# usb.net
KiCad netlist of a schematic drawn in Altium Designer
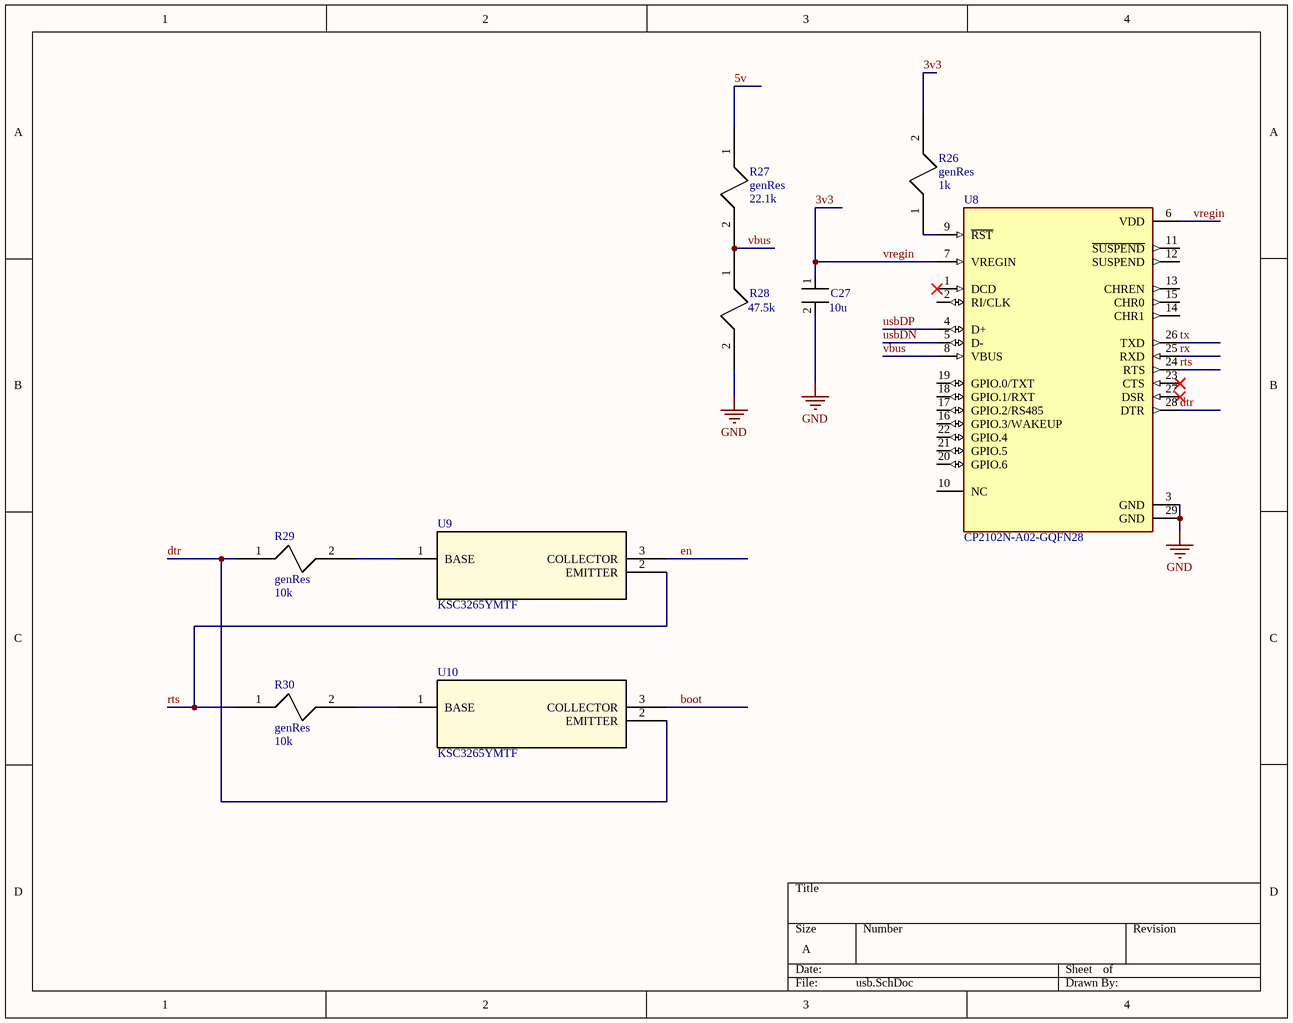
[diagram p0: usb.SchDoc]

(export (version "E")
  (design (tool "Eeschema 10.0.6"))
  (components
    (comp (ref "C27")
      (value "genCap")
      (footprint "GeneralCap")
      (description "C6119842")
      (fields (field (name "C") "10u"))
      (libsource (lib "seniorDesign") (part "genCap"))
    )
    (comp (ref "R26")
      (value "genRes")
      (footprint "GeneralCap")
      (description "C22548")
      (fields (field (name "R") "1k"))
      (libsource (lib "seniorDesign") (part "genRes"))
    )
    (comp (ref "R27")
      (value "genRes")
      (footprint "GeneralCap")
      (description "C137768")
      (fields (field (name "R") "22.1k"))
      (libsource (lib "seniorDesign") (part "genRes"))
    )
    (comp (ref "R28")
      (value "genRes")
      (footprint "GeneralCap")
      (description "C705990")
      (fields (field (name "R") "47.5k"))
      (libsource (lib "seniorDesign") (part "genRes"))
    )
    (comp (ref "R29")
      (value "genRes")
      (footprint "GeneralCap")
      (description "C98220")
      (fields (field (name "R") "10k"))
      (libsource (lib "seniorDesign") (part "genRes"))
    )
    (comp (ref "R30")
      (value "genRes")
      (footprint "GeneralCap")
      (description "C98220")
      (fields (field (name "R") "10k"))
      (libsource (lib "seniorDesign") (part "genRes"))
    )
    (comp (ref "U8")
      (value "CP2102N-A02-GQFN28")
      (footprint "QFN50P500X500X80-29N")
      (description "C1550553")
      (fields (field (name "MF") "Silicon Labs"))
      (libsource (lib "CP2102N-A02-GQFN28") (part "CP2102N-A02-GQFN28"))
    )
    (comp (ref "U9")
      (value "KSC3265YMTF")
      (footprint "SOT-23_ONS")
      (description "C14809")
      (libsource (lib "KSC3265YMTF") (part "KSC3265YMTF"))
    )
    (comp (ref "U10")
      (value "KSC3265YMTF")
      (footprint "SOT-23_ONS")
      (description "C14809")
      (libsource (lib "KSC3265YMTF") (part "KSC3265YMTF"))
    )
  )
  (nets
    (net (code "1") (name "/3v3") (class "Default")
      (node (ref "C27") (pin "1") (pinfunction "1_1") (pintype "passive"))
      (node (ref "R26") (pin "2") (pinfunction "2_2") (pintype "passive"))
      (node (ref "U8") (pin "6") (pinfunction "VDD_6") (pintype "power_in"))
      (node (ref "U8") (pin "7") (pinfunction "VREGIN_7") (pintype "input"))
    )
    (net (code "2") (name "/5v") (class "Default")
      (node (ref "R27") (pin "1") (pinfunction "1_1") (pintype "passive"))
    )
    (net (code "3") (name "/boot") (class "Default")
      (node (ref "U10") (pin "3") (pinfunction "COLLECTOR_3") (pintype "passive"))
    )
    (net (code "4") (name "/dtr") (class "Default")
      (node (ref "R29") (pin "1") (pinfunction "1_1") (pintype "passive"))
      (node (ref "U10") (pin "2") (pinfunction "EMITTER_2") (pintype "passive"))
      (node (ref "U8") (pin "28") (pinfunction "DTR_28") (pintype "output"))
    )
    (net (code "5") (name "/en") (class "Default")
      (node (ref "U9") (pin "3") (pinfunction "COLLECTOR_3") (pintype "passive"))
    )
    (net (code "6") (name "/rts") (class "Default")
      (node (ref "R30") (pin "1") (pinfunction "1_1") (pintype "passive"))
      (node (ref "U8") (pin "24") (pinfunction "RTS_24") (pintype "output"))
      (node (ref "U9") (pin "2") (pinfunction "EMITTER_2") (pintype "passive"))
    )
    (net (code "7") (name "/rx") (class "Default")
      (node (ref "U8") (pin "25") (pinfunction "RXD_25") (pintype "input"))
    )
    (net (code "8") (name "/tx") (class "Default")
      (node (ref "U8") (pin "26") (pinfunction "TXD_26") (pintype "output"))
    )
    (net (code "9") (name "/usbDN") (class "Default")
      (node (ref "U8") (pin "5") (pinfunction "D-_5") (pintype "bidirectional"))
    )
    (net (code "10") (name "/usbDP") (class "Default")
      (node (ref "U8") (pin "4") (pinfunction "D+_4") (pintype "bidirectional"))
    )
    (net (code "11") (name "/vbus") (class "Default")
      (node (ref "R27") (pin "2") (pinfunction "2_2") (pintype "passive"))
      (node (ref "R28") (pin "1") (pinfunction "1_1") (pintype "passive"))
      (node (ref "U8") (pin "8") (pinfunction "VBUS_8") (pintype "input"))
    )
    (net (code "12") (name "GND") (class "Default")
      (node (ref "C27") (pin "2") (pinfunction "2_2") (pintype "passive"))
      (node (ref "R28") (pin "2") (pinfunction "2_2") (pintype "passive"))
      (node (ref "U8") (pin "29") (pinfunction "GND_29") (pintype "power_in"))
      (node (ref "U8") (pin "3") (pinfunction "GND_3") (pintype "power_in"))
    )
    (net (code "13") (name "Net-(U8-~{RST})") (class "Default")
      (node (ref "R26") (pin "1") (pinfunction "1_1") (pintype "passive"))
      (node (ref "U8") (pin "9") (pinfunction "~{RST}_9") (pintype "input"))
    )
    (net (code "14") (name "Net-(U9-BASE)") (class "Default")
      (node (ref "R29") (pin "2") (pinfunction "2_2") (pintype "passive"))
      (node (ref "U9") (pin "1") (pinfunction "BASE_1") (pintype "passive"))
    )
    (net (code "15") (name "Net-(U10-BASE)") (class "Default")
      (node (ref "R30") (pin "2") (pinfunction "2_2") (pintype "passive"))
      (node (ref "U10") (pin "1") (pinfunction "BASE_1") (pintype "passive"))
    )
    (net (code "16") (name "unconnected-(U8-CHR0-Pad15)") (class "Default")
      (node (ref "U8") (pin "15") (pinfunction "CHR0_15") (pintype "output"))
    )
    (net (code "17") (name "unconnected-(U8-CHR1-Pad14)") (class "Default")
      (node (ref "U8") (pin "14") (pinfunction "CHR1_14") (pintype "output"))
    )
    (net (code "18") (name "unconnected-(U8-CHREN-Pad13)") (class "Default")
      (node (ref "U8") (pin "13") (pinfunction "CHREN_13") (pintype "output"))
    )
    (net (code "19") (name "unconnected-(U8-CTS-Pad23)") (class "Default")
      (node (ref "U8") (pin "23") (pinfunction "CTS_23") (pintype "input+no_connect"))
    )
    (net (code "20") (name "unconnected-(U8-DCD-Pad1)") (class "Default")
      (node (ref "U8") (pin "1") (pinfunction "DCD_1") (pintype "input+no_connect"))
    )
    (net (code "21") (name "unconnected-(U8-DSR-Pad27)") (class "Default")
      (node (ref "U8") (pin "27") (pinfunction "DSR_27") (pintype "input+no_connect"))
    )
    (net (code "22") (name "unconnected-(U8-GPIO.0{slash}TXT-Pad19)") (class "Default")
      (node (ref "U8") (pin "19") (pinfunction "GPIO.0/TXT_19") (pintype "bidirectional"))
    )
    (net (code "23") (name "unconnected-(U8-GPIO.1{slash}RXT-Pad18)") (class "Default")
      (node (ref "U8") (pin "18") (pinfunction "GPIO.1/RXT_18") (pintype "bidirectional"))
    )
    (net (code "24") (name "unconnected-(U8-GPIO.2{slash}RS485-Pad17)") (class "Default")
      (node (ref "U8") (pin "17") (pinfunction "GPIO.2/RS485_17") (pintype "bidirectional"))
    )
    (net (code "25") (name "unconnected-(U8-GPIO.3{slash}WAKEUP-Pad16)") (class "Default")
      (node (ref "U8") (pin "16") (pinfunction "GPIO.3/WAKEUP_16") (pintype "bidirectional"))
    )
    (net (code "26") (name "unconnected-(U8-GPIO.4-Pad22)") (class "Default")
      (node (ref "U8") (pin "22") (pinfunction "GPIO.4_22") (pintype "bidirectional"))
    )
    (net (code "27") (name "unconnected-(U8-GPIO.5-Pad21)") (class "Default")
      (node (ref "U8") (pin "21") (pinfunction "GPIO.5_21") (pintype "bidirectional"))
    )
    (net (code "28") (name "unconnected-(U8-GPIO.6-Pad20)") (class "Default")
      (node (ref "U8") (pin "20") (pinfunction "GPIO.6_20") (pintype "bidirectional"))
    )
    (net (code "29") (name "unconnected-(U8-NC-Pad10)") (class "Default")
      (node (ref "U8") (pin "10") (pinfunction "NC_10") (pintype "passive"))
    )
    (net (code "30") (name "unconnected-(U8-RI{slash}CLK-Pad2)") (class "Default")
      (node (ref "U8") (pin "2") (pinfunction "RI/CLK_2") (pintype "bidirectional"))
    )
    (net (code "31") (name "unconnected-(U8-SUSPEND-Pad12)") (class "Default")
      (node (ref "U8") (pin "12") (pinfunction "SUSPEND_12") (pintype "output"))
    )
    (net (code "32") (name "unconnected-(U8-~{SUSPEND}-Pad11)") (class "Default")
      (node (ref "U8") (pin "11") (pinfunction "~{SUSPEND}_11") (pintype "output"))
    )
  )
)
